# Firetruck_-_arduino_uno_shield_-_EasyEDA.net
KiCad netlist of a schematic drawn in EasyEDA
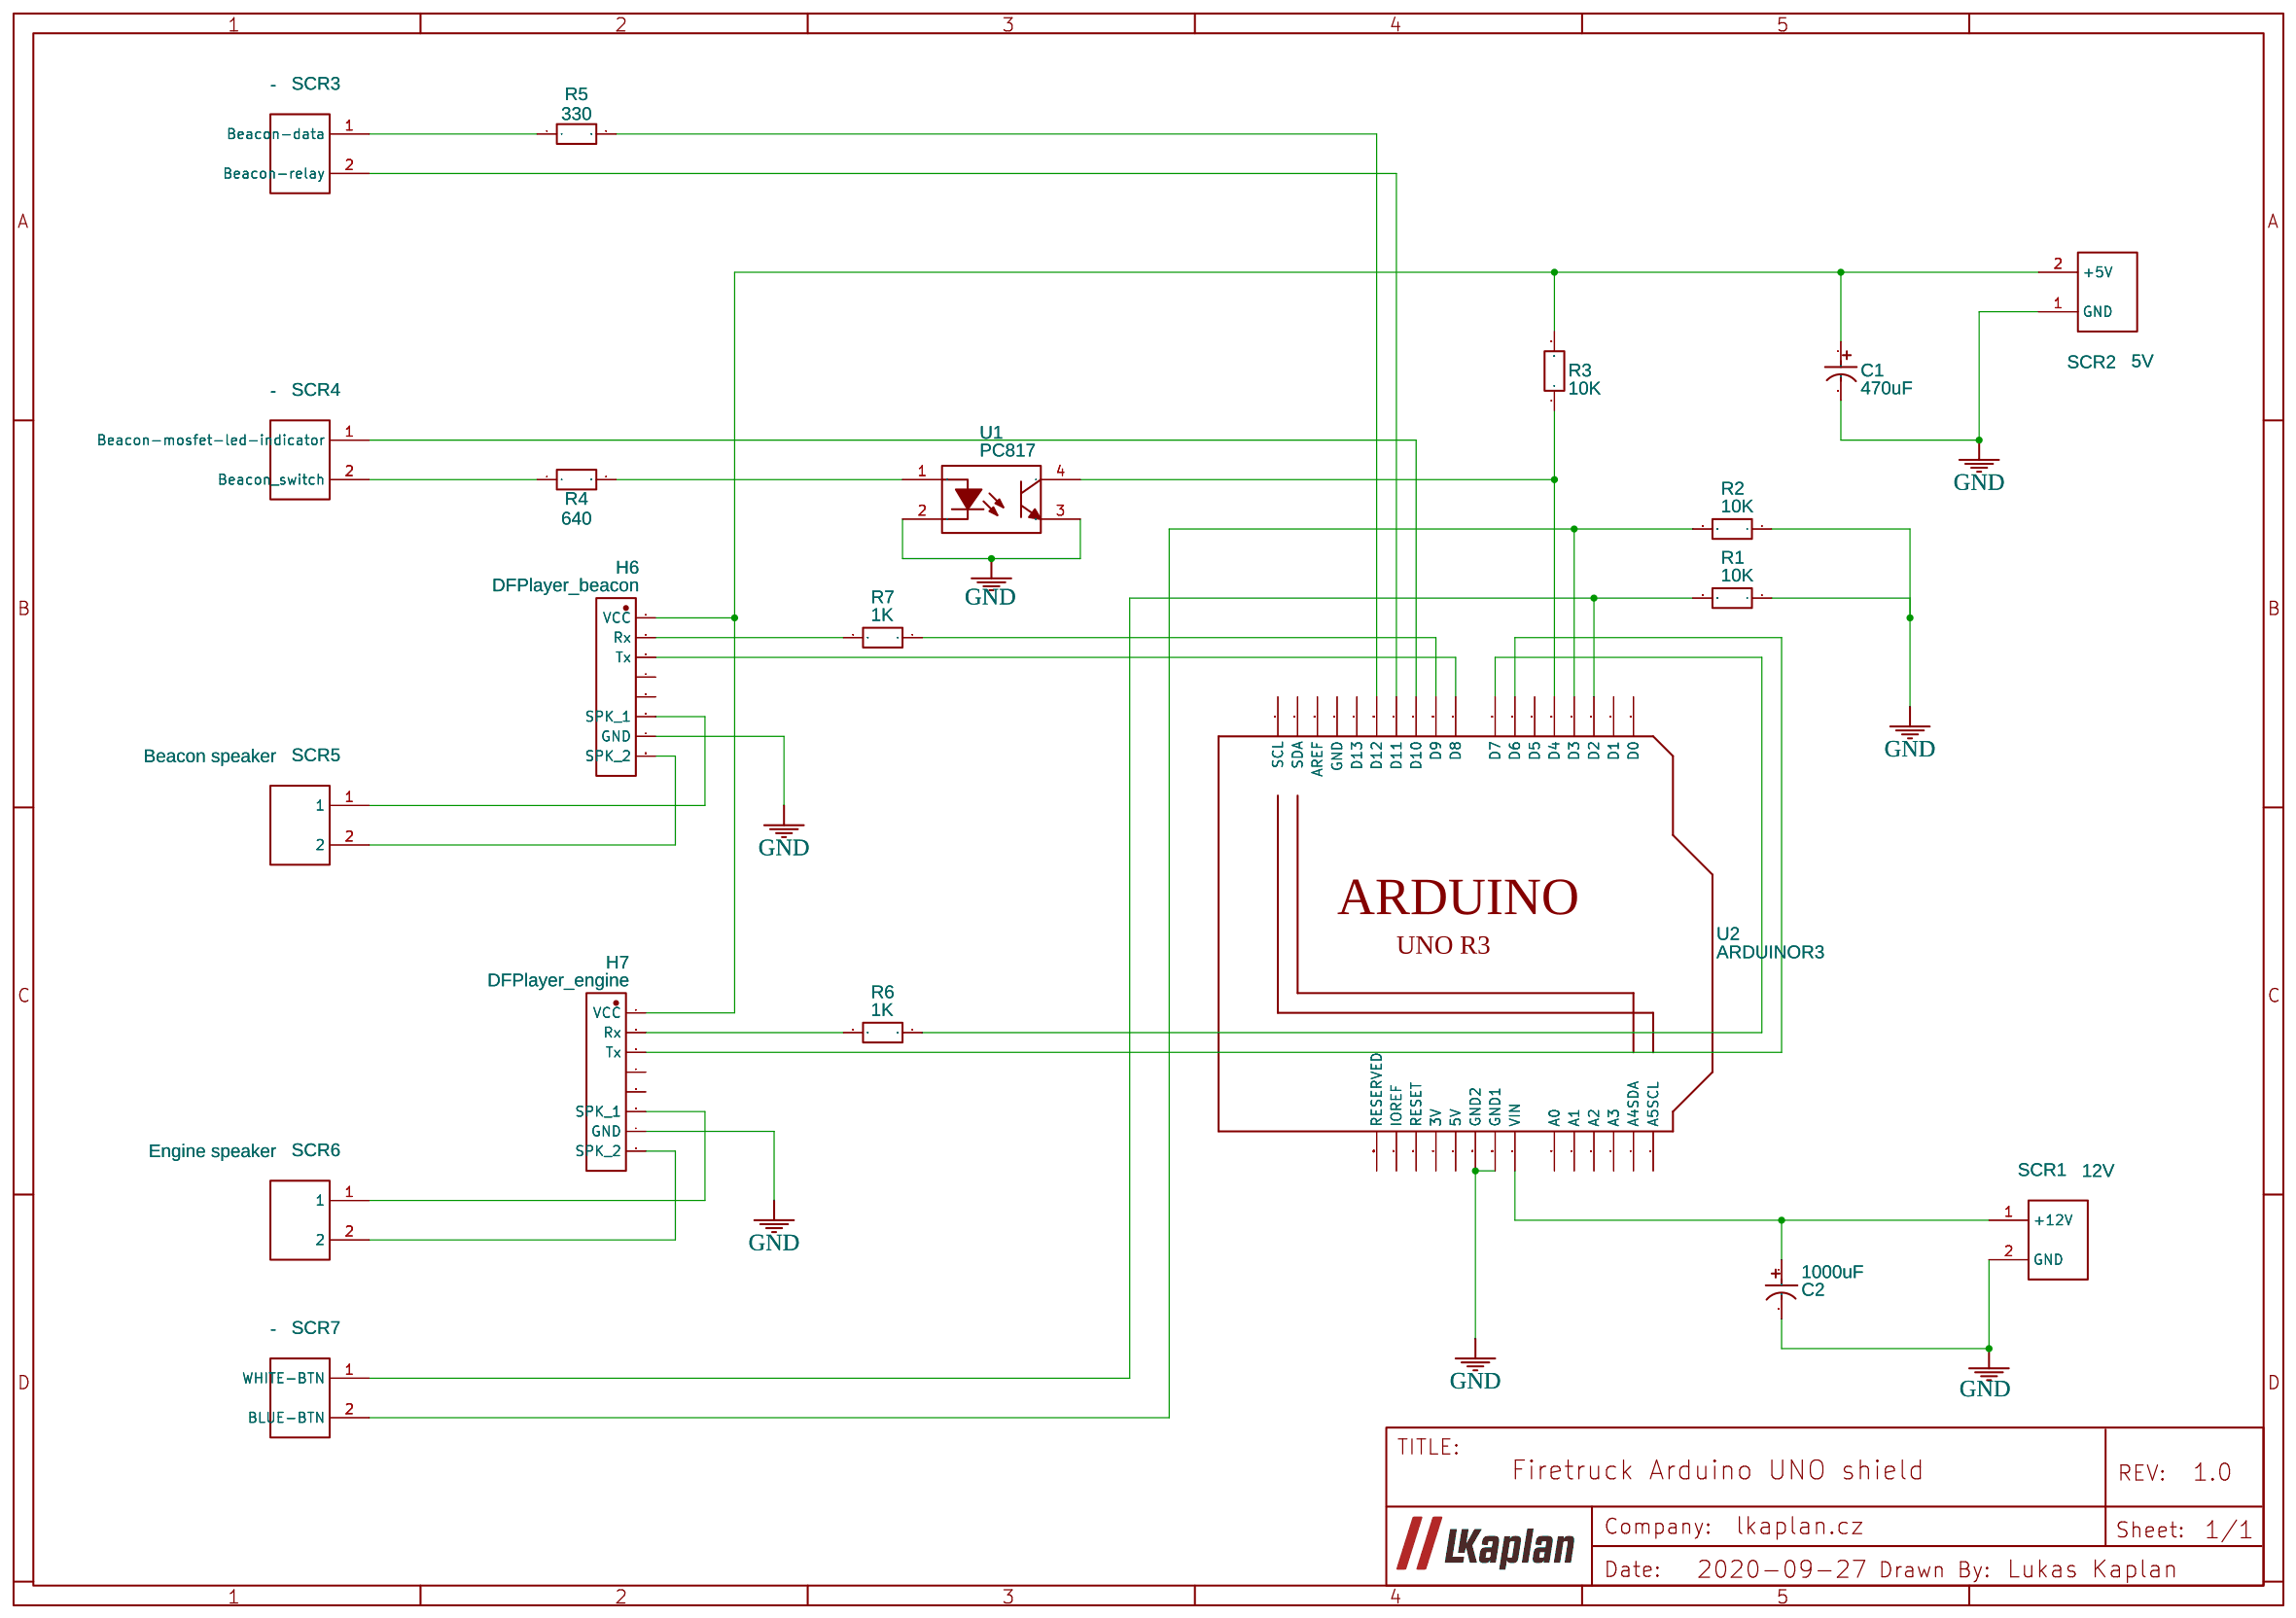
[diagram p0: schematic sheet]

(export (version "E")
  (design (tool "Eeschema 10.0.6"))
  (components
    (comp (ref "C1")
      (value "470uF")
      (fields
        (field (name "BOM_Manufacturer Part") "470uF 16V绿金 8*12")
        (field (name "BOM_Supplier Part") "C43823")
      )
      (libsource (lib "") (part "470uF 16V绿金 8*12"))
    )
    (comp (ref "C2")
      (value "1000uF")
      (fields
        (field (name "BOM_Manufacturer Part") "1000uF 16V 10*16")
        (field (name "BOM_Supplier Part") "C43831")
      )
      (libsource (lib "") (part "1000uF 16V 10*16"))
    )
    (comp (ref "H6")
      (value "DFPlayer_beacon")
      (fields (field (name "BOM_Manufacturer Part") "215297-8") (field (name "BOM_Supplier Part") "C306180"))
      (libsource (lib "") (part "215297-8"))
    )
    (comp (ref "H7")
      (value "DFPlayer_engine")
      (fields (field (name "BOM_Manufacturer Part") "215297-8") (field (name "BOM_Supplier Part") "C306180"))
      (libsource (lib "") (part "215297-8"))
    )
    (comp (ref "R1")
      (value "10K")
      (fields
        (field (name "BOM_Manufacturer Part") "MO1/4W-22K±5%-ST52")
        (field (name "BOM_Supplier Part") "C479388")
      )
      (libsource (lib "") (part "MO1/4W-22K±5%-ST52"))
    )
    (comp (ref "R2")
      (value "10K")
      (fields
        (field (name "BOM_Manufacturer Part") "MO1/4W-22K±5%-ST52")
        (field (name "BOM_Supplier Part") "C479388")
      )
      (libsource (lib "") (part "MO1/4W-22K±5%-ST52"))
    )
    (comp (ref "R3")
      (value "10K")
      (fields
        (field (name "BOM_Manufacturer Part") "MO1/4W-22K±5%-ST52")
        (field (name "BOM_Supplier Part") "C479388")
      )
      (libsource (lib "") (part "MO1/4W-22K±5%-ST52_2"))
    )
    (comp (ref "R4")
      (value "640")
      (fields
        (field (name "BOM_Manufacturer Part") "MO1/4W-22K±5%-ST52")
        (field (name "BOM_Supplier Part") "C479388")
      )
      (libsource (lib "") (part "MO1/4W-22K±5%-ST52_1"))
    )
    (comp (ref "R5")
      (value "330")
      (fields
        (field (name "BOM_Manufacturer Part") "MO1/4W-22K±5%-ST52")
        (field (name "BOM_Supplier Part") "C479388")
      )
      (libsource (lib "") (part "MO1/4W-22K±5%-ST52_1"))
    )
    (comp (ref "R6")
      (value "1K")
      (fields
        (field (name "BOM_Manufacturer Part") "MO1/4W-22K±5%-ST52")
        (field (name "BOM_Supplier Part") "C479388")
      )
      (libsource (lib "") (part "MO1/4W-22K±5%-ST52"))
    )
    (comp (ref "R7")
      (value "1K")
      (fields
        (field (name "BOM_Manufacturer Part") "MO1/4W-22K±5%-ST52")
        (field (name "BOM_Supplier Part") "C479388")
      )
      (libsource (lib "") (part "MO1/4W-22K±5%-ST52"))
    )
    (comp (ref "SCR1")
      (value "12V")
      (fields
        (field (name "BOM_Manufacturer Part") "MKDSN1.5/2-5.08")
        (field (name "BOM_Supplier Part") "C91153")
      )
      (libsource (lib "") (part "MKDSN1.5/2-5.08_4"))
    )
    (comp (ref "SCR2")
      (value "5V")
      (fields
        (field (name "BOM_Manufacturer Part") "MKDSN1.5/2-5.08")
        (field (name "BOM_Supplier Part") "C91153")
      )
      (libsource (lib "") (part "MKDSN1.5/2-5.08_1"))
    )
    (comp (ref "SCR3")
      (value "-")
      (fields
        (field (name "BOM_Manufacturer Part") "MKDSN1.5/2-5.08")
        (field (name "BOM_Supplier Part") "C91153")
      )
      (libsource (lib "") (part "MKDSN1.5/2-5.08"))
    )
    (comp (ref "SCR4")
      (value "-")
      (fields
        (field (name "BOM_Manufacturer Part") "MKDSN1.5/2-5.08")
        (field (name "BOM_Supplier Part") "C91153")
      )
      (libsource (lib "") (part "MKDSN1.5/2-5.08_3"))
    )
    (comp (ref "SCR5")
      (value "Beacon speaker")
      (fields
        (field (name "BOM_Manufacturer Part") "MKDSN1.5/2-5.08")
        (field (name "BOM_Supplier Part") "C91153")
      )
      (libsource (lib "") (part "MKDSN1.5/2-5.08_2"))
    )
    (comp (ref "SCR6")
      (value "Engine speaker")
      (fields
        (field (name "BOM_Manufacturer Part") "MKDSN1.5/2-5.08")
        (field (name "BOM_Supplier Part") "C91153")
      )
      (libsource (lib "") (part "MKDSN1.5/2-5.08_2"))
    )
    (comp (ref "SCR7")
      (value "-")
      (fields
        (field (name "BOM_Manufacturer Part") "MKDSN1.5/2-5.08")
        (field (name "BOM_Supplier Part") "C91153")
      )
      (libsource (lib "") (part "MKDSN1.5/2-5.08_5"))
    )
    (comp (ref "U1")
      (value "PC817")
      (fields
        (field (name "BOM_Manufacturer Part") "PC817X3NSZW(C )")
        (field (name "BOM_Supplier Part") "C4075")
      )
      (libsource (lib "") (part "PC817X3NSZW(C )"))
    )
    (comp (ref "U2") (value "ARDUINOR3") (libsource (lib "") (part "ARDUINOR3")))
  )
  (nets
    (net (code "1") (name "GND") (class "Default")
      (node (ref "C1") (pin "2") (pinfunction "2_2") (pintype "input"))
      (node (ref "C2") (pin "2") (pinfunction "2_2") (pintype "input"))
      (node (ref "H6") (pin "7") (pinfunction "GND_7") (pintype "unspecified"))
      (node (ref "H7") (pin "7") (pinfunction "GND_7") (pintype "unspecified"))
      (node (ref "R1") (pin "1") (pinfunction "1_1") (pintype "unspecified"))
      (node (ref "R2") (pin "1") (pinfunction "1_1") (pintype "unspecified"))
      (node (ref "SCR1") (pin "2") (pinfunction "GND_2") (pintype "unspecified"))
      (node (ref "SCR2") (pin "1") (pinfunction "GND_1") (pintype "unspecified"))
      (node (ref "U1") (pin "2") (pinfunction "2_2") (pintype "unspecified"))
      (node (ref "U1") (pin "3") (pinfunction "3_3") (pintype "unspecified"))
      (node (ref "U2") (pin "GND1") (pinfunction "GND1_GND1") (pintype "passive"))
      (node (ref "U2") (pin "GND2") (pinfunction "GND2_GND2") (pintype "passive"))
    )
    (net (code "2") (name "Net-(H6-Rx)") (class "Default")
      (node (ref "H6") (pin "2") (pinfunction "Rx_2") (pintype "unspecified"))
      (node (ref "R7") (pin "2") (pinfunction "2_2") (pintype "unspecified"))
    )
    (net (code "3") (name "Net-(H6-SPK_1)") (class "Default")
      (node (ref "H6") (pin "6") (pinfunction "SPK_1_6") (pintype "unspecified"))
      (node (ref "SCR5") (pin "1") (pinfunction "1_1") (pintype "unspecified"))
    )
    (net (code "4") (name "Net-(H6-SPK_2)") (class "Default")
      (node (ref "H6") (pin "8") (pinfunction "SPK_2_8") (pintype "unspecified"))
      (node (ref "SCR5") (pin "2") (pinfunction "2_2") (pintype "unspecified"))
    )
    (net (code "5") (name "Net-(H6-Tx)") (class "Default")
      (node (ref "H6") (pin "3") (pinfunction "Tx_3") (pintype "unspecified"))
      (node (ref "U2") (pin "D8") (pinfunction "D8_D8") (pintype "unspecified"))
    )
    (net (code "6") (name "Net-(H6-VCC)") (class "Default")
      (node (ref "C1") (pin "1") (pinfunction "1_1") (pintype "input"))
      (node (ref "H6") (pin "1") (pinfunction "VCC_1") (pintype "unspecified"))
      (node (ref "H7") (pin "1") (pinfunction "VCC_1") (pintype "unspecified"))
      (node (ref "R3") (pin "2") (pinfunction "2_2") (pintype "unspecified"))
      (node (ref "SCR2") (pin "2") (pinfunction "+5V_2") (pintype "unspecified"))
    )
    (net (code "7") (name "Net-(H7-Rx)") (class "Default")
      (node (ref "H7") (pin "2") (pinfunction "Rx_2") (pintype "unspecified"))
      (node (ref "R6") (pin "2") (pinfunction "2_2") (pintype "unspecified"))
    )
    (net (code "8") (name "Net-(H7-SPK_1)") (class "Default")
      (node (ref "H7") (pin "6") (pinfunction "SPK_1_6") (pintype "unspecified"))
      (node (ref "SCR6") (pin "1") (pinfunction "1_1") (pintype "unspecified"))
    )
    (net (code "9") (name "Net-(H7-SPK_2)") (class "Default")
      (node (ref "H7") (pin "8") (pinfunction "SPK_2_8") (pintype "unspecified"))
      (node (ref "SCR6") (pin "2") (pinfunction "2_2") (pintype "unspecified"))
    )
    (net (code "10") (name "Net-(H7-Tx)") (class "Default")
      (node (ref "H7") (pin "3") (pinfunction "Tx_3") (pintype "unspecified"))
      (node (ref "U2") (pin "D6") (pinfunction "D6_D6") (pintype "unspecified"))
    )
    (net (code "11") (name "Net-(R3-Pad1)") (class "Default")
      (node (ref "R3") (pin "1") (pinfunction "1_1") (pintype "unspecified"))
      (node (ref "U1") (pin "4") (pinfunction "4_4") (pintype "unspecified"))
      (node (ref "U2") (pin "D4") (pinfunction "D4_D4") (pintype "unspecified"))
    )
    (net (code "12") (name "Net-(R4-Pad2)") (class "Default")
      (node (ref "R4") (pin "2") (pinfunction "2_2") (pintype "unspecified"))
      (node (ref "U1") (pin "1") (pinfunction "1_1") (pintype "unspecified"))
    )
    (net (code "13") (name "Net-(R5-Pad2)") (class "Default")
      (node (ref "R5") (pin "2") (pinfunction "2_2") (pintype "unspecified"))
      (node (ref "U2") (pin "D12") (pinfunction "D12_D12") (pintype "unspecified"))
    )
    (net (code "14") (name "Net-(R6-Pad1)") (class "Default")
      (node (ref "R6") (pin "1") (pinfunction "1_1") (pintype "unspecified"))
      (node (ref "U2") (pin "D7") (pinfunction "D7_D7") (pintype "unspecified"))
    )
    (net (code "15") (name "Net-(R7-Pad1)") (class "Default")
      (node (ref "R7") (pin "1") (pinfunction "1_1") (pintype "unspecified"))
      (node (ref "U2") (pin "D9") (pinfunction "D9_D9") (pintype "unspecified"))
    )
    (net (code "16") (name "Net-(SCR1-+12V)") (class "Default")
      (node (ref "C2") (pin "1") (pinfunction "1_1") (pintype "input"))
      (node (ref "SCR1") (pin "1") (pinfunction "+12V_1") (pintype "unspecified"))
      (node (ref "U2") (pin "VIN") (pinfunction "VIN_VIN") (pintype "passive"))
    )
    (net (code "17") (name "Net-(SCR3-Beacon-data)") (class "Default")
      (node (ref "R5") (pin "1") (pinfunction "1_1") (pintype "unspecified"))
      (node (ref "SCR3") (pin "1") (pinfunction "Beacon-data_1") (pintype "unspecified"))
    )
    (net (code "18") (name "Net-(SCR3-Beacon-relay)") (class "Default")
      (node (ref "SCR3") (pin "2") (pinfunction "Beacon-relay_2") (pintype "unspecified"))
      (node (ref "U2") (pin "D11") (pinfunction "D11_D11") (pintype "unspecified"))
    )
    (net (code "19") (name "Net-(SCR4-Beacon-mosfet-led-indicator)") (class "Default")
      (node (ref "SCR4") (pin "1") (pinfunction "Beacon-mosfet-led-indicator_1") (pintype "unspecified"))
      (node (ref "U2") (pin "D10") (pinfunction "D10_D10") (pintype "unspecified"))
    )
    (net (code "20") (name "Net-(SCR4-Beacon_switch)") (class "Default")
      (node (ref "R4") (pin "1") (pinfunction "1_1") (pintype "unspecified"))
      (node (ref "SCR4") (pin "2") (pinfunction "Beacon_switch_2") (pintype "unspecified"))
    )
    (net (code "21") (name "Net-(SCR7-BLUE-BTN)") (class "Default")
      (node (ref "R2") (pin "2") (pinfunction "2_2") (pintype "unspecified"))
      (node (ref "SCR7") (pin "2") (pinfunction "BLUE-BTN_2") (pintype "unspecified"))
      (node (ref "U2") (pin "D3") (pinfunction "D3_D3") (pintype "unspecified"))
    )
    (net (code "22") (name "Net-(SCR7-WHITE-BTN)") (class "Default")
      (node (ref "R1") (pin "2") (pinfunction "2_2") (pintype "unspecified"))
      (node (ref "SCR7") (pin "1") (pinfunction "WHITE-BTN_1") (pintype "unspecified"))
      (node (ref "U2") (pin "D2") (pinfunction "D2_D2") (pintype "unspecified"))
    )
    (net (code "23") (name "unconnected-(H6-Pad4)") (class "Default")
      (node (ref "H6") (pin "4") (pintype "unspecified"))
    )
    (net (code "24") (name "unconnected-(H6-Pad5)") (class "Default")
      (node (ref "H6") (pin "5") (pintype "unspecified"))
    )
    (net (code "25") (name "unconnected-(H7-Pad4)") (class "Default")
      (node (ref "H7") (pin "4") (pintype "unspecified"))
    )
    (net (code "26") (name "unconnected-(H7-Pad5)") (class "Default")
      (node (ref "H7") (pin "5") (pintype "unspecified"))
    )
    (net (code "27") (name "unconnected-(U2-A4SDA-PadA4)") (class "Default")
      (node (ref "U2") (pin "A4") (pinfunction "A4SDA_A4") (pintype "unspecified"))
    )
    (net (code "28") (name "unconnected-(U2-A5SCL-PadA5)") (class "Default")
      (node (ref "U2") (pin "A5") (pinfunction "A5SCL_A5") (pintype "unspecified"))
    )
    (net (code "29") (name "unconnected-(U2-Pad3V)") (class "Default")
      (node (ref "U2") (pin "3V") (pinfunction "3V_3V") (pintype "passive"))
    )
    (net (code "30") (name "unconnected-(U2-Pad5V)") (class "Default")
      (node (ref "U2") (pin "5V") (pinfunction "5V_5V") (pintype "passive"))
    )
    (net (code "31") (name "unconnected-(U2-PadA0)") (class "Default")
      (node (ref "U2") (pin "A0") (pinfunction "A0_A0") (pintype "unspecified"))
    )
    (net (code "32") (name "unconnected-(U2-PadA1)") (class "Default")
      (node (ref "U2") (pin "A1") (pinfunction "A1_A1") (pintype "unspecified"))
    )
    (net (code "33") (name "unconnected-(U2-PadA2)") (class "Default")
      (node (ref "U2") (pin "A2") (pinfunction "A2_A2") (pintype "unspecified"))
    )
    (net (code "34") (name "unconnected-(U2-PadA3)") (class "Default")
      (node (ref "U2") (pin "A3") (pinfunction "A3_A3") (pintype "unspecified"))
    )
    (net (code "35") (name "unconnected-(U2-PadAREF)") (class "Default")
      (node (ref "U2") (pin "AREF") (pinfunction "AREF_AREF") (pintype "unspecified"))
    )
    (net (code "36") (name "unconnected-(U2-PadD0)") (class "Default")
      (node (ref "U2") (pin "D0") (pinfunction "D0_D0") (pintype "unspecified"))
    )
    (net (code "37") (name "unconnected-(U2-PadD1)") (class "Default")
      (node (ref "U2") (pin "D1") (pinfunction "D1_D1") (pintype "unspecified"))
    )
    (net (code "38") (name "unconnected-(U2-PadD5)") (class "Default")
      (node (ref "U2") (pin "D5") (pinfunction "D5_D5") (pintype "unspecified"))
    )
    (net (code "39") (name "unconnected-(U2-PadD13)") (class "Default")
      (node (ref "U2") (pin "D13") (pinfunction "D13_D13") (pintype "unspecified"))
    )
    (net (code "40") (name "unconnected-(U2-PadGND)") (class "Default")
      (node (ref "U2") (pin "GND") (pinfunction "GND_GND") (pintype "passive"))
    )
    (net (code "41") (name "unconnected-(U2-PadIOREF)") (class "Default")
      (node (ref "U2") (pin "IOREF") (pinfunction "IOREF_IOREF") (pintype "output"))
    )
    (net (code "42") (name "unconnected-(U2-PadRESERVED)") (class "Default")
      (node (ref "U2") (pin "RESERVED") (pinfunction "RESERVED_RESERVED") (pintype "unspecified"))
    )
    (net (code "43") (name "unconnected-(U2-PadRESET)") (class "Default")
      (node (ref "U2") (pin "RESET") (pinfunction "RESET_RESET") (pintype "unspecified"))
    )
    (net (code "44") (name "unconnected-(U2-PadSCL)") (class "Default")
      (node (ref "U2") (pin "SCL") (pinfunction "SCL_SCL") (pintype "unspecified"))
    )
    (net (code "45") (name "unconnected-(U2-PadSDA)") (class "Default")
      (node (ref "U2") (pin "SDA") (pinfunction "SDA_SDA") (pintype "unspecified"))
    )
  )
)
